# tick-mini-mk-2_1.net
KiCad netlist of a schematic drawn in EAGLE
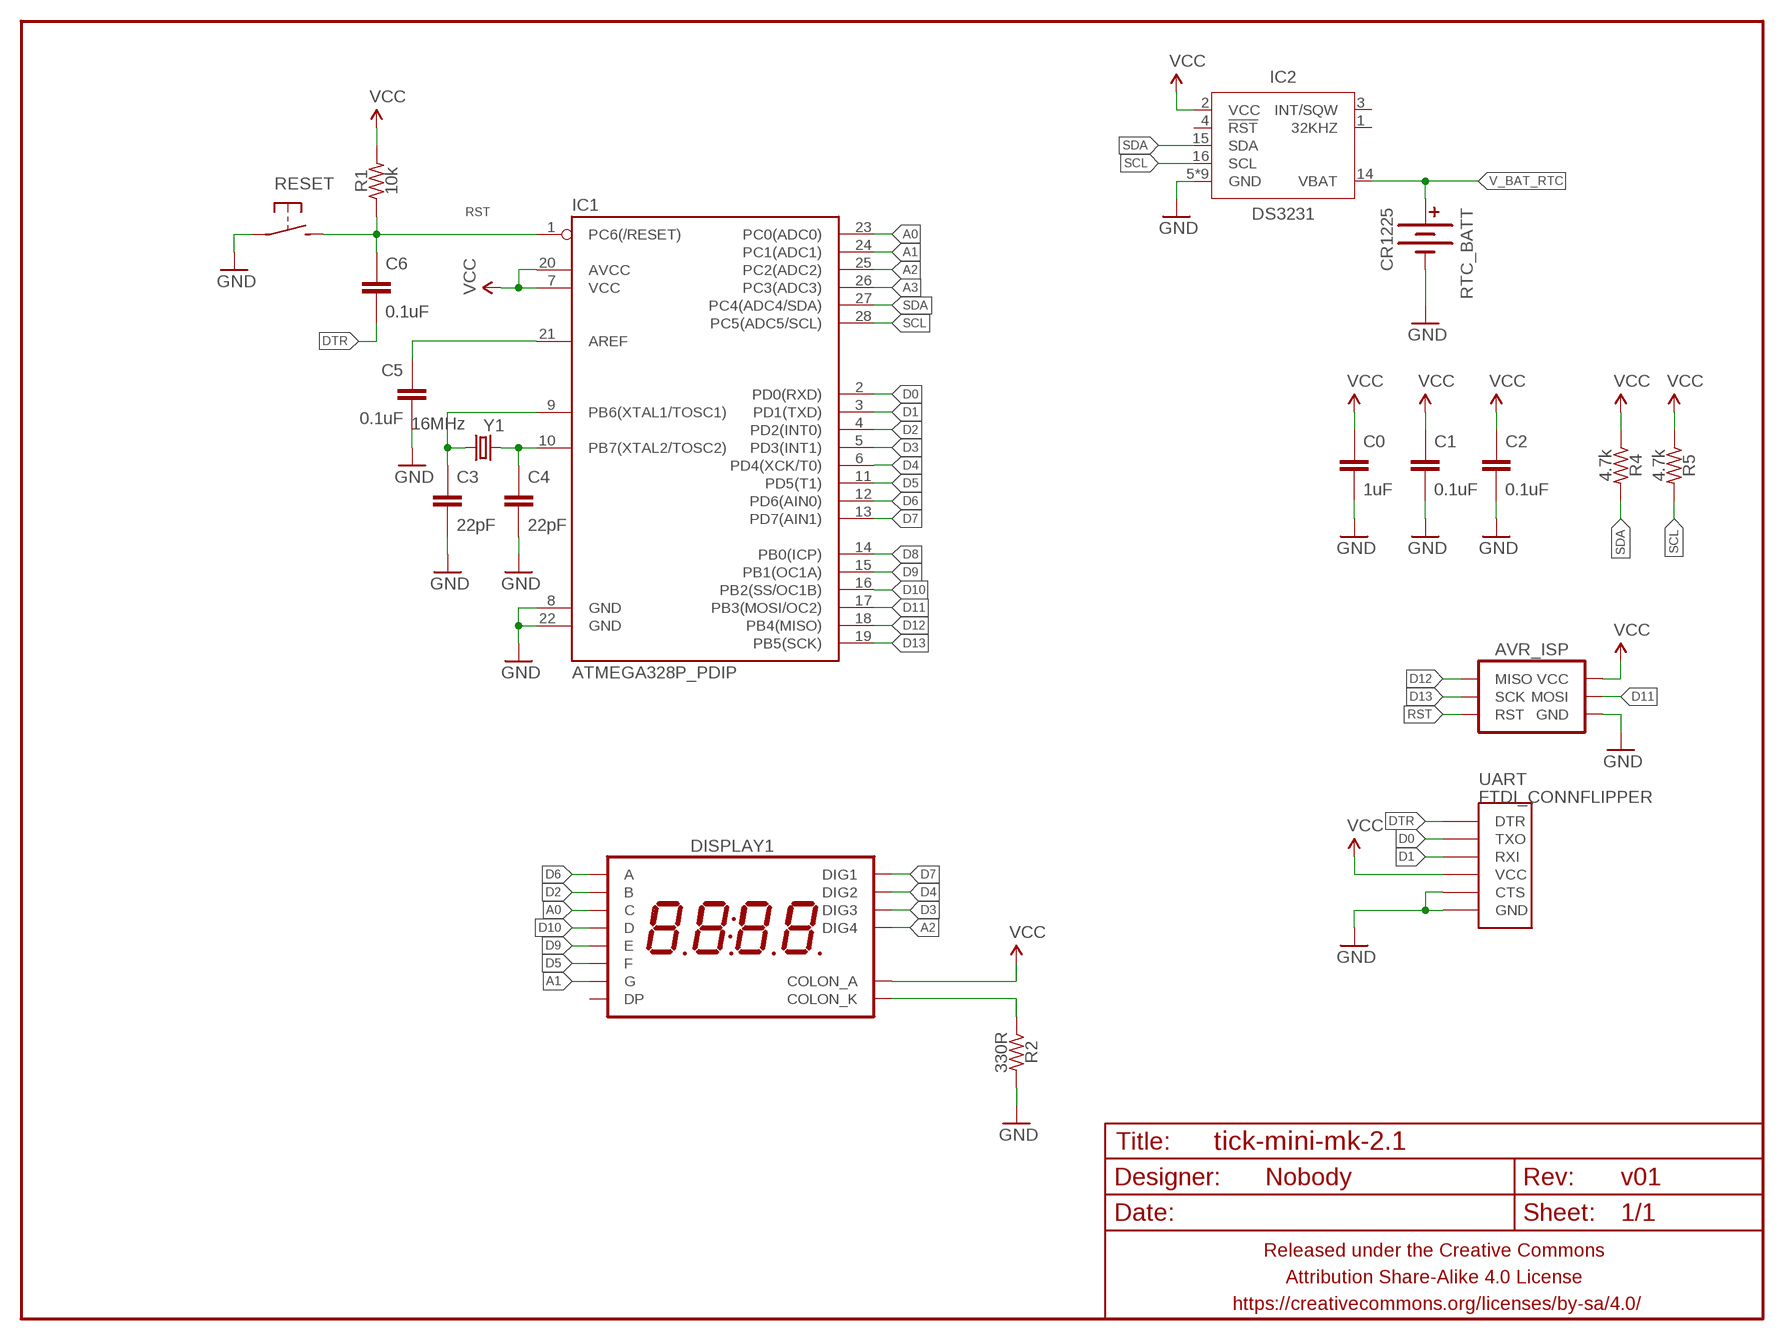
[diagram p0: schematic, sheet 1]

(export (version "E")
  (design (tool "Eeschema 10.0.6"))
  (components
    (comp (ref "AVR_ISP")
      (value "AVR_SPI_PRG_6INLINE")
      (footprint "eagle-import:AVR_MINI_PROG")
      (libsource (lib "eagle-import") (part "AVR_SPI_PRG_6INLINE"))
    )
    (comp (ref "C0")
      (value "1uF")
      (footprint "eagle-import:C025-024X044")
      (libsource (lib "eagle-import") (part "CAPACITOR-CERAMIC025-024X044"))
    )
    (comp (ref "C1")
      (value "0.1uF")
      (footprint "eagle-import:C025-024X044")
      (libsource (lib "eagle-import") (part "CAPACITOR-CERAMIC025-024X044"))
    )
    (comp (ref "C2")
      (value "0.1uF")
      (footprint "eagle-import:C025-024X044")
      (libsource (lib "eagle-import") (part "CAPACITOR-CERAMIC025-024X044"))
    )
    (comp (ref "C3")
      (value "22pF")
      (footprint "eagle-import:C025-024X044")
      (libsource (lib "eagle-import") (part "CAPACITOR-CERAMIC025-024X044"))
    )
    (comp (ref "C4")
      (value "22pF")
      (footprint "eagle-import:C025-024X044")
      (libsource (lib "eagle-import") (part "CAPACITOR-CERAMIC025-024X044"))
    )
    (comp (ref "C5")
      (value "0.1uF")
      (footprint "eagle-import:C025-024X044")
      (libsource (lib "eagle-import") (part "CAPACITOR-CERAMIC025-024X044"))
    )
    (comp (ref "C6")
      (value "0.1uF")
      (footprint "eagle-import:C025-024X044")
      (libsource (lib "eagle-import") (part "CAPACITOR-CERAMIC025-024X044"))
    )
    (comp (ref "DISPLAY1")
      (value "7SEG_4DIGIT_COLON14.2MM-CC-NS")
      (footprint "eagle-import:7SEG_4DIG_NS")
      (libsource (lib "eagle-import") (part "7SEG_4DIGIT_COLON14.2MM-CC-NS"))
    )
    (comp (ref "FRAME1")
      (value "FRAME-LETTERNO_PACKAGE")
      (footprint "eagle-import:DUMMY")
      (fields (field (name "DESIGNER") "Nobody"))
      (libsource (lib "eagle-import") (part "FRAME-LETTERNO_PACKAGE"))
    )
    (comp (ref "IC1")
      (value "ATMEGA328P_PDIP")
      (footprint "eagle-import:DIL28-3")
      (libsource (lib "eagle-import") (part "ATMEGA328P_PDIP"))
    )
    (comp (ref "IC2")
      (value "DS3231")
      (footprint "eagle-import:SO16W")
      (libsource (lib "eagle-import") (part "DS3231"))
    )
    (comp (ref "R1")
      (value "10k")
      (footprint "eagle-import:RESISTOR-AXIAL-PTH-7.62MM")
      (libsource (lib "eagle-import") (part "RESISTORPTH-AXIAL-7.62MM"))
    )
    (comp (ref "R2")
      (value "330R")
      (footprint "eagle-import:RESISTOR-AXIAL-PTH-7.62MM")
      (libsource (lib "eagle-import") (part "RESISTORPTH-AXIAL-7.62MM"))
    )
    (comp (ref "R4")
      (value "4.7k")
      (footprint "eagle-import:RESISTOR-AXIAL-PTH-7.62MM")
      (libsource (lib "eagle-import") (part "RESISTORPTH-AXIAL-7.62MM"))
    )
    (comp (ref "R5")
      (value "4.7k")
      (footprint "eagle-import:RESISTOR-AXIAL-PTH-7.62MM")
      (libsource (lib "eagle-import") (part "RESISTORPTH-AXIAL-7.62MM"))
    )
    (comp (ref "RESET")
      (value "SPST-NO-TACT3MM-RA")
      (footprint "eagle-import:TACTILE-PTH-SIDE")
      (libsource (lib "eagle-import") (part "SPST-NO-TACT3MM-RA"))
    )
    (comp (ref "RTC_BATT")
      (value "CR1225")
      (footprint "eagle-import:BATTCON_12MM")
      (libsource (lib "eagle-import") (part "BATTERY12MM"))
    )
    (comp (ref "UART")
      (value "FTDI_CONNFLIPPER")
      (footprint "eagle-import:FTDI_CONN_FLIP")
      (libsource (lib "eagle-import") (part "FTDI_CONNFLIPPER"))
    )
    (comp (ref "Y1")
      (value "16MHz")
      (footprint "eagle-import:HC49U-V")
      (libsource (lib "eagle-import") (part "CRYSTALHC49UV"))
    )
  )
  (nets
    (net (code "1") (name "A0") (class "Default")
      (node (ref "DISPLAY1") (pin "P$4") (pinfunction "C_P$4") (pintype "passive"))
      (node (ref "IC1") (pin "23") (pinfunction "PC0(ADC0)_23") (pintype "bidirectional"))
    )
    (net (code "2") (name "A1") (class "Default")
      (node (ref "DISPLAY1") (pin "P$5") (pinfunction "G_P$5") (pintype "passive"))
      (node (ref "IC1") (pin "24") (pinfunction "PC1(ADC1)_24") (pintype "bidirectional"))
    )
    (net (code "3") (name "A2") (class "Default")
      (node (ref "DISPLAY1") (pin "P$6") (pinfunction "DIG4_P$6") (pintype "passive"))
      (node (ref "IC1") (pin "25") (pinfunction "PC2(ADC2)_25") (pintype "bidirectional"))
    )
    (net (code "4") (name "A3") (class "Default")
      (node (ref "IC1") (pin "26") (pinfunction "PC3(ADC3)_26") (pintype "bidirectional"))
    )
    (net (code "5") (name "D0") (class "Default")
      (node (ref "IC1") (pin "2") (pinfunction "PD0(RXD)_2") (pintype "bidirectional"))
      (node (ref "UART") (pin "TXO") (pinfunction "TXO_TXO") (pintype "bidirectional"))
    )
    (net (code "6") (name "D1") (class "Default")
      (node (ref "IC1") (pin "3") (pinfunction "PD1(TXD)_3") (pintype "bidirectional"))
      (node (ref "UART") (pin "RXI") (pinfunction "RXI_RXI") (pintype "bidirectional"))
    )
    (net (code "7") (name "D2") (class "Default")
      (node (ref "DISPLAY1") (pin "P$9") (pinfunction "B_P$9") (pintype "passive"))
      (node (ref "IC1") (pin "4") (pinfunction "PD2(INT0)_4") (pintype "bidirectional"))
    )
    (net (code "8") (name "D3") (class "Default")
      (node (ref "DISPLAY1") (pin "P$10") (pinfunction "DIG3_P$10") (pintype "passive"))
      (node (ref "IC1") (pin "5") (pinfunction "PD3(INT1)_5") (pintype "bidirectional"))
    )
    (net (code "9") (name "D4") (class "Default")
      (node (ref "DISPLAY1") (pin "P$11") (pinfunction "DIG2_P$11") (pintype "passive"))
      (node (ref "IC1") (pin "6") (pinfunction "PD4(XCK/T0)_6") (pintype "bidirectional"))
    )
    (net (code "10") (name "D5") (class "Default")
      (node (ref "DISPLAY1") (pin "P$12") (pinfunction "F_P$12") (pintype "passive"))
      (node (ref "IC1") (pin "11") (pinfunction "PD5(T1)_11") (pintype "bidirectional"))
    )
    (net (code "11") (name "D6") (class "Default")
      (node (ref "DISPLAY1") (pin "P$13") (pinfunction "A_P$13") (pintype "passive"))
      (node (ref "IC1") (pin "12") (pinfunction "PD6(AIN0)_12") (pintype "bidirectional"))
    )
    (net (code "12") (name "D7") (class "Default")
      (node (ref "DISPLAY1") (pin "P$14") (pinfunction "DIG1_P$14") (pintype "passive"))
      (node (ref "IC1") (pin "13") (pinfunction "PD7(AIN1)_13") (pintype "bidirectional"))
    )
    (net (code "13") (name "D8") (class "Default")
      (node (ref "IC1") (pin "14") (pinfunction "PB0(ICP)_14") (pintype "bidirectional"))
    )
    (net (code "14") (name "D9") (class "Default")
      (node (ref "DISPLAY1") (pin "P$1") (pinfunction "E_P$1") (pintype "passive"))
      (node (ref "IC1") (pin "15") (pinfunction "PB1(OC1A)_15") (pintype "bidirectional"))
    )
    (net (code "15") (name "D10") (class "Default")
      (node (ref "DISPLAY1") (pin "P$2") (pinfunction "D_P$2") (pintype "passive"))
      (node (ref "IC1") (pin "16") (pinfunction "PB2(SS/OC1B)_16") (pintype "bidirectional"))
    )
    (net (code "16") (name "D11") (class "Default")
      (node (ref "AVR_ISP") (pin "4") (pinfunction "MOSI_4") (pintype "passive"))
      (node (ref "IC1") (pin "17") (pinfunction "PB3(MOSI/OC2)_17") (pintype "bidirectional"))
    )
    (net (code "17") (name "D12") (class "Default")
      (node (ref "AVR_ISP") (pin "1") (pinfunction "MISO_1") (pintype "passive"))
      (node (ref "IC1") (pin "18") (pinfunction "PB4(MISO)_18") (pintype "bidirectional"))
    )
    (net (code "18") (name "D13") (class "Default")
      (node (ref "AVR_ISP") (pin "3") (pinfunction "SCK_3") (pintype "passive"))
      (node (ref "IC1") (pin "19") (pinfunction "PB5(SCK)_19") (pintype "bidirectional"))
    )
    (net (code "19") (name "DTR") (class "Default")
      (node (ref "C6") (pin "2") (pinfunction "2_2") (pintype "passive"))
      (node (ref "UART") (pin "DTR") (pinfunction "DTR_DTR") (pintype "bidirectional"))
    )
    (net (code "20") (name "GND") (class "Default")
      (node (ref "AVR_ISP") (pin "6") (pinfunction "GND_6") (pintype "passive"))
      (node (ref "C0") (pin "2") (pinfunction "2_2") (pintype "passive"))
      (node (ref "C1") (pin "2") (pinfunction "2_2") (pintype "passive"))
      (node (ref "C2") (pin "2") (pinfunction "2_2") (pintype "passive"))
      (node (ref "C3") (pin "2") (pinfunction "2_2") (pintype "passive"))
      (node (ref "C4") (pin "2") (pinfunction "2_2") (pintype "passive"))
      (node (ref "C5") (pin "2") (pinfunction "2_2") (pintype "passive"))
      (node (ref "IC1") (pin "22") (pinfunction "GND_22") (pintype "bidirectional"))
      (node (ref "IC1") (pin "8") (pinfunction "GND_8") (pintype "bidirectional"))
      (node (ref "IC2") (pin "10") (pinfunction "GND_10") (pintype "bidirectional"))
      (node (ref "IC2") (pin "11") (pinfunction "GND_11") (pintype "bidirectional"))
      (node (ref "IC2") (pin "12") (pinfunction "GND_12") (pintype "bidirectional"))
      (node (ref "IC2") (pin "13") (pinfunction "GND_13") (pintype "bidirectional"))
      (node (ref "IC2") (pin "5") (pinfunction "GND_5") (pintype "bidirectional"))
      (node (ref "IC2") (pin "6") (pinfunction "GND_6") (pintype "bidirectional"))
      (node (ref "IC2") (pin "7") (pinfunction "GND_7") (pintype "bidirectional"))
      (node (ref "IC2") (pin "8") (pinfunction "GND_8") (pintype "bidirectional"))
      (node (ref "IC2") (pin "9") (pinfunction "GND_9") (pintype "bidirectional"))
      (node (ref "R2") (pin "P$2") (pinfunction "2_P$2") (pintype "passive"))
      (node (ref "RESET") (pin "1") (pinfunction "1_1") (pintype "passive"))
      (node (ref "RTC_BATT") (pin "GND") (pinfunction "-_GND") (pintype "power_in"))
      (node (ref "UART") (pin "CTS") (pinfunction "CTS_CTS") (pintype "bidirectional"))
      (node (ref "UART") (pin "GND") (pinfunction "GND_GND") (pintype "bidirectional"))
    )
    (net (code "21") (name "Net-(DISPLAY1-COLON_K)") (class "Default")
      (node (ref "DISPLAY1") (pin "P$7") (pinfunction "COLON_K_P$7") (pintype "passive"))
      (node (ref "R2") (pin "P$1") (pinfunction "1_P$1") (pintype "passive"))
    )
    (net (code "22") (name "Net-(IC1-AREF)") (class "Default")
      (node (ref "C5") (pin "1") (pinfunction "1_1") (pintype "passive"))
      (node (ref "IC1") (pin "21") (pinfunction "AREF_21") (pintype "bidirectional"))
    )
    (net (code "23") (name "Net-(IC1-PB6(XTAL1{slash}TOSC1))") (class "Default")
      (node (ref "C3") (pin "1") (pinfunction "1_1") (pintype "passive"))
      (node (ref "IC1") (pin "9") (pinfunction "PB6(XTAL1/TOSC1)_9") (pintype "bidirectional"))
      (node (ref "Y1") (pin "2") (pinfunction "2_2") (pintype "passive"))
    )
    (net (code "24") (name "Net-(IC1-PB7(XTAL2{slash}TOSC2))") (class "Default")
      (node (ref "C4") (pin "1") (pinfunction "1_1") (pintype "passive"))
      (node (ref "IC1") (pin "10") (pinfunction "PB7(XTAL2/TOSC2)_10") (pintype "bidirectional"))
      (node (ref "Y1") (pin "1") (pinfunction "1_1") (pintype "passive"))
    )
    (net (code "25") (name "RST") (class "Default")
      (node (ref "AVR_ISP") (pin "5") (pinfunction "RST_5") (pintype "passive"))
      (node (ref "C6") (pin "1") (pinfunction "1_1") (pintype "passive"))
      (node (ref "IC1") (pin "1") (pinfunction "PC6(/RESET)_1") (pintype "bidirectional"))
      (node (ref "R1") (pin "P$1") (pinfunction "1_P$1") (pintype "passive"))
      (node (ref "RESET") (pin "2") (pinfunction "2_2") (pintype "passive"))
    )
    (net (code "26") (name "SCL") (class "Default")
      (node (ref "IC1") (pin "28") (pinfunction "PC5(ADC5/SCL)_28") (pintype "bidirectional"))
      (node (ref "IC2") (pin "16") (pinfunction "SCL_16") (pintype "bidirectional"))
      (node (ref "R5") (pin "P$2") (pinfunction "2_P$2") (pintype "passive"))
    )
    (net (code "27") (name "SDA") (class "Default")
      (node (ref "IC1") (pin "27") (pinfunction "PC4(ADC4/SDA)_27") (pintype "bidirectional"))
      (node (ref "IC2") (pin "15") (pinfunction "SDA_15") (pintype "bidirectional"))
      (node (ref "R4") (pin "P$2") (pinfunction "2_P$2") (pintype "passive"))
    )
    (net (code "28") (name "VCC") (class "Default")
      (node (ref "AVR_ISP") (pin "2") (pinfunction "VCC_2") (pintype "passive"))
      (node (ref "C0") (pin "1") (pinfunction "1_1") (pintype "passive"))
      (node (ref "C1") (pin "1") (pinfunction "1_1") (pintype "passive"))
      (node (ref "C2") (pin "1") (pinfunction "1_1") (pintype "passive"))
      (node (ref "DISPLAY1") (pin "P$8") (pinfunction "COLON_A_P$8") (pintype "passive"))
      (node (ref "IC1") (pin "20") (pinfunction "AVCC_20") (pintype "bidirectional"))
      (node (ref "IC1") (pin "7") (pinfunction "VCC_7") (pintype "bidirectional"))
      (node (ref "IC2") (pin "2") (pinfunction "VCC_2") (pintype "bidirectional"))
      (node (ref "R1") (pin "P$2") (pinfunction "2_P$2") (pintype "passive"))
      (node (ref "R4") (pin "P$1") (pinfunction "1_P$1") (pintype "passive"))
      (node (ref "R5") (pin "P$1") (pinfunction "1_P$1") (pintype "passive"))
      (node (ref "UART") (pin "VCC") (pinfunction "VCC_VCC") (pintype "bidirectional"))
    )
    (net (code "29") (name "V_BAT_RTC") (class "Default")
      (node (ref "IC2") (pin "14") (pinfunction "VBAT_14") (pintype "bidirectional"))
      (node (ref "RTC_BATT") (pin "PWR@1") (pinfunction "+_PWR@1") (pintype "power_in"))
    )
    (net (code "30") (name "unconnected-(DISPLAY1-DP-PadP$3)") (class "Default")
      (node (ref "DISPLAY1") (pin "P$3") (pinfunction "DP_P$3") (pintype "passive"))
    )
    (net (code "31") (name "unconnected-(IC2-32KHZ-Pad1)") (class "Default")
      (node (ref "IC2") (pin "1") (pinfunction "32KHZ_1") (pintype "bidirectional"))
    )
    (net (code "32") (name "unconnected-(IC2-INT{slash}SQW-Pad3)") (class "Default")
      (node (ref "IC2") (pin "3") (pinfunction "INT/SQW_3") (pintype "bidirectional"))
    )
    (net (code "33") (name "unconnected-(IC2-~{RST}-Pad4)") (class "Default")
      (node (ref "IC2") (pin "4") (pinfunction "~{RST}_4") (pintype "bidirectional"))
    )
  )
)
